# Reflectance_Sensors_SCH.net
KiCad netlist of a schematic drawn in Altium Designer
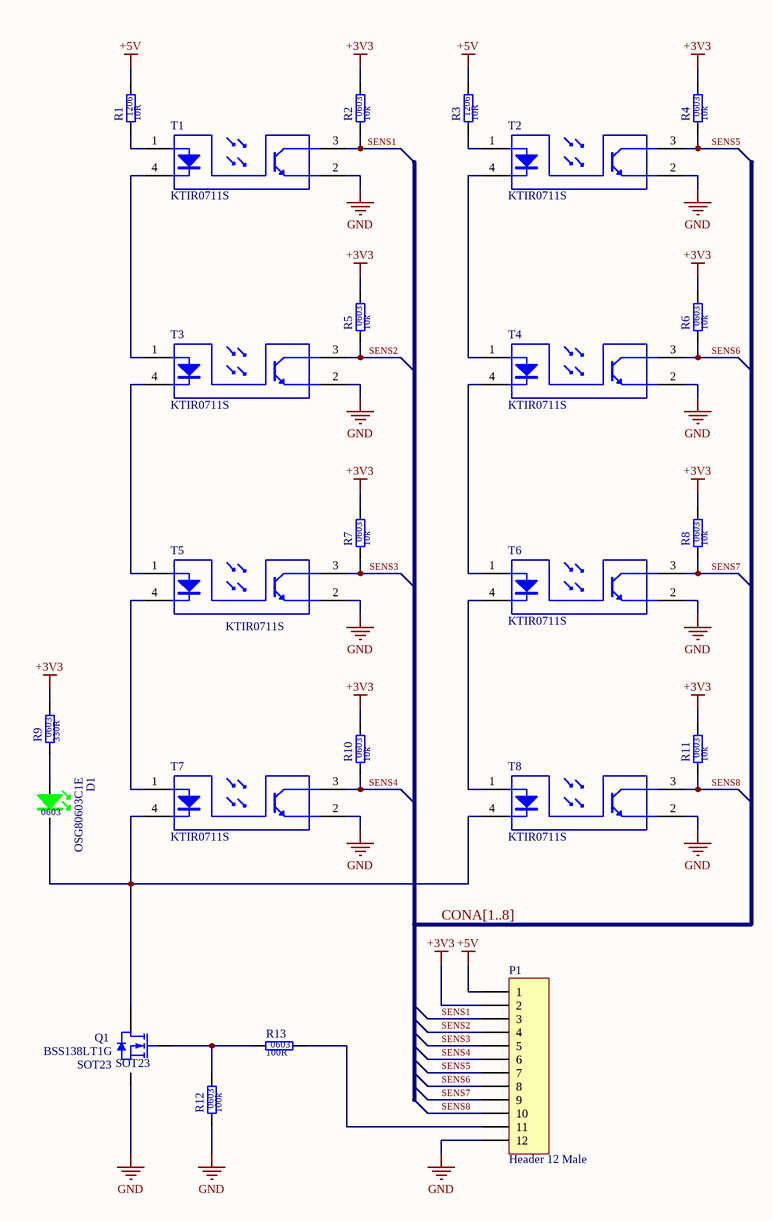
[diagram p0: Reflectance_Sensors_SCH.SchDoc]

(export (version "E")
  (design (tool "Eeschema 10.0.6"))
  (components
    (comp (ref "D1")
      (value "OSG80603C1E")
      (footprint "OL_0603_1608")
      (description "LED GREEN")
      (fields
        (field (name "SCH_FOOTPRINT") "0603")
        (field (name "PART NUMBER") "OL_G_0603_OSG80603C1E")
        (field (name "MANUFACTURER") "Optosupply")
      )
      (libsource (lib "Library") (part "OL_G"))
    )
    (comp (ref "P1")
      (value "Header 12 Male")
      (footprint "H1X12_LONG")
      (description "Header, 12-Pin")
      (libsource (lib "Miscellaneous Connectors") (part "Header 12"))
    )
    (comp (ref "Q1")
      (value "BSS138LT1G")
      (footprint "SOT23_TO236_SC59")
      (fields
        (field (name "PART NUMBER") "QNS_BSS138LT1G_50V_0A2")
        (field (name "SCH_FOOTPRINT") "SOT23")
        (field (name "VOLTAGE") "50V")
        (field (name "MANUFACTURER") "ON Semiconductor")
      )
      (libsource (lib "Library") (part "QN_GSD"))
    )
    (comp (ref "R1")
      (value "10R")
      (footprint "R_1206")
      (fields
        (field (name "SCH_FOOTPRINT") "1206")
        (field (name "PART NUMBER") "R_10R_1206_1")
        (field (name "VOLTAGE") "200V")
        (field (name "POWER") "250mW")
      )
      (libsource (lib "Library") (part "R"))
    )
    (comp (ref "R2")
      (value "10k")
      (footprint "R_0603")
      (fields
        (field (name "SCH_FOOTPRINT") "0603")
        (field (name "PART NUMBER") "R_10k_0603_1")
        (field (name "VOLTAGE") "75V")
        (field (name "POWER") "100mW")
      )
      (libsource (lib "Library") (part "R"))
    )
    (comp (ref "R3")
      (value "10R")
      (footprint "R_1206")
      (fields
        (field (name "SCH_FOOTPRINT") "1206")
        (field (name "PART NUMBER") "R_10R_1206_1")
        (field (name "VOLTAGE") "200V")
        (field (name "POWER") "250mW")
      )
      (libsource (lib "Library") (part "R"))
    )
    (comp (ref "R4")
      (value "10k")
      (footprint "R_0603")
      (fields
        (field (name "SCH_FOOTPRINT") "0603")
        (field (name "PART NUMBER") "R_10k_0603_1")
        (field (name "VOLTAGE") "75V")
        (field (name "POWER") "100mW")
      )
      (libsource (lib "Library") (part "R"))
    )
    (comp (ref "R5")
      (value "10k")
      (footprint "R_0603")
      (fields
        (field (name "SCH_FOOTPRINT") "0603")
        (field (name "PART NUMBER") "R_10k_0603_1")
        (field (name "VOLTAGE") "75V")
        (field (name "POWER") "100mW")
      )
      (libsource (lib "Library") (part "R"))
    )
    (comp (ref "R6")
      (value "10k")
      (footprint "R_0603")
      (fields
        (field (name "SCH_FOOTPRINT") "0603")
        (field (name "PART NUMBER") "R_10k_0603_1")
        (field (name "VOLTAGE") "75V")
        (field (name "POWER") "100mW")
      )
      (libsource (lib "Library") (part "R"))
    )
    (comp (ref "R7")
      (value "10k")
      (footprint "R_0603")
      (fields
        (field (name "SCH_FOOTPRINT") "0603")
        (field (name "PART NUMBER") "R_10k_0603_1")
        (field (name "VOLTAGE") "75V")
        (field (name "POWER") "100mW")
      )
      (libsource (lib "Library") (part "R"))
    )
    (comp (ref "R8")
      (value "10k")
      (footprint "R_0603")
      (fields
        (field (name "SCH_FOOTPRINT") "0603")
        (field (name "PART NUMBER") "R_10k_0603_1")
        (field (name "VOLTAGE") "75V")
        (field (name "POWER") "100mW")
      )
      (libsource (lib "Library") (part "R"))
    )
    (comp (ref "R9")
      (value "330R")
      (footprint "R_0603")
      (fields
        (field (name "SCH_FOOTPRINT") "0603")
        (field (name "PART NUMBER") "R_330R_0603_1")
        (field (name "VOLTAGE") "50V")
        (field (name "POWER") "100mW")
      )
      (libsource (lib "Library") (part "R"))
    )
    (comp (ref "R10")
      (value "10k")
      (footprint "R_0603")
      (fields
        (field (name "SCH_FOOTPRINT") "0603")
        (field (name "PART NUMBER") "R_10k_0603_1")
        (field (name "VOLTAGE") "75V")
        (field (name "POWER") "100mW")
      )
      (libsource (lib "Library") (part "R"))
    )
    (comp (ref "R11")
      (value "10k")
      (footprint "R_0603")
      (fields
        (field (name "SCH_FOOTPRINT") "0603")
        (field (name "PART NUMBER") "R_10k_0603_1")
        (field (name "VOLTAGE") "75V")
        (field (name "POWER") "100mW")
      )
      (libsource (lib "Library") (part "R"))
    )
    (comp (ref "R12")
      (value "100k")
      (footprint "R_0603")
      (fields
        (field (name "SCH_FOOTPRINT") "0603")
        (field (name "PART NUMBER") "R_100k_0603_1")
        (field (name "VOLTAGE") "50V")
        (field (name "POWER") "100mW")
      )
      (libsource (lib "Library") (part "R"))
    )
    (comp (ref "R13")
      (value "100R")
      (footprint "R_0603")
      (fields
        (field (name "SCH_FOOTPRINT") "0603")
        (field (name "PART NUMBER") "R_100R_0603_1")
        (field (name "VOLTAGE") "50V")
        (field (name "POWER") "100mW")
      )
      (libsource (lib "Library") (part "R"))
    )
    (comp (ref "T1")
      (value "KTIR0711S")
      (footprint "KTIR0711S")
      (libsource (lib "Linefollower") (part "KTIR0711S"))
    )
    (comp (ref "T2")
      (value "KTIR0711S")
      (footprint "KTIR0711S")
      (libsource (lib "Linefollower") (part "KTIR0711S"))
    )
    (comp (ref "T3")
      (value "KTIR0711S")
      (footprint "KTIR0711S")
      (libsource (lib "Linefollower") (part "KTIR0711S"))
    )
    (comp (ref "T4")
      (value "KTIR0711S")
      (footprint "KTIR0711S")
      (libsource (lib "Linefollower") (part "KTIR0711S"))
    )
    (comp (ref "T5")
      (value "KTIR0711S")
      (footprint "KTIR0711S")
      (libsource (lib "Linefollower") (part "KTIR0711S"))
    )
    (comp (ref "T6")
      (value "KTIR0711S")
      (footprint "KTIR0711S")
      (libsource (lib "Linefollower") (part "KTIR0711S"))
    )
    (comp (ref "T7")
      (value "KTIR0711S")
      (footprint "KTIR0711S")
      (libsource (lib "Linefollower") (part "KTIR0711S"))
    )
    (comp (ref "T8")
      (value "KTIR0711S")
      (footprint "KTIR0711S")
      (libsource (lib "Linefollower") (part "KTIR0711S"))
    )
  )
  (nets
    (net (code "9") (name "+3V3") (class "Default")
      (node (ref "P1") (pin "2") (pinfunction "2_2") (pintype "passive"))
      (node (ref "R10") (pin "2") (pinfunction "2_2") (pintype "passive"))
      (node (ref "R11") (pin "2") (pinfunction "2_2") (pintype "passive"))
      (node (ref "R2") (pin "2") (pinfunction "2_2") (pintype "passive"))
      (node (ref "R4") (pin "2") (pinfunction "2_2") (pintype "passive"))
      (node (ref "R5") (pin "2") (pinfunction "2_2") (pintype "passive"))
      (node (ref "R6") (pin "2") (pinfunction "2_2") (pintype "passive"))
      (node (ref "R7") (pin "2") (pinfunction "2_2") (pintype "passive"))
      (node (ref "R8") (pin "2") (pinfunction "2_2") (pintype "passive"))
      (node (ref "R9") (pin "2") (pinfunction "2_2") (pintype "passive"))
    )
    (net (code "10") (name "+5V") (class "Default")
      (node (ref "P1") (pin "1") (pinfunction "1_1") (pintype "passive"))
      (node (ref "R1") (pin "2") (pinfunction "2_2") (pintype "passive"))
      (node (ref "R3") (pin "2") (pinfunction "2_2") (pintype "passive"))
    )
    (net (code "12") (name "/SENS1") (class "Default")
      (node (ref "P1") (pin "3") (pinfunction "3_3") (pintype "passive"))
      (node (ref "R2") (pin "1") (pinfunction "1_1") (pintype "passive"))
      (node (ref "T1") (pin "3") (pinfunction "C_3") (pintype "passive"))
    )
    (net (code "13") (name "/SENS2") (class "Default")
      (node (ref "P1") (pin "4") (pinfunction "4_4") (pintype "passive"))
      (node (ref "R5") (pin "1") (pinfunction "1_1") (pintype "passive"))
      (node (ref "T3") (pin "3") (pinfunction "C_3") (pintype "passive"))
    )
    (net (code "14") (name "/SENS3") (class "Default")
      (node (ref "P1") (pin "5") (pinfunction "5_5") (pintype "passive"))
      (node (ref "R7") (pin "1") (pinfunction "1_1") (pintype "passive"))
      (node (ref "T5") (pin "3") (pinfunction "C_3") (pintype "passive"))
    )
    (net (code "15") (name "/SENS4") (class "Default")
      (node (ref "P1") (pin "6") (pinfunction "6_6") (pintype "passive"))
      (node (ref "R10") (pin "1") (pinfunction "1_1") (pintype "passive"))
      (node (ref "T7") (pin "3") (pinfunction "C_3") (pintype "passive"))
    )
    (net (code "16") (name "/SENS5") (class "Default")
      (node (ref "P1") (pin "7") (pinfunction "7_7") (pintype "passive"))
      (node (ref "R4") (pin "1") (pinfunction "1_1") (pintype "passive"))
      (node (ref "T2") (pin "3") (pinfunction "C_3") (pintype "passive"))
    )
    (net (code "17") (name "/SENS6") (class "Default")
      (node (ref "P1") (pin "8") (pinfunction "8_8") (pintype "passive"))
      (node (ref "R6") (pin "1") (pinfunction "1_1") (pintype "passive"))
      (node (ref "T4") (pin "3") (pinfunction "C_3") (pintype "passive"))
    )
    (net (code "18") (name "/SENS7") (class "Default")
      (node (ref "P1") (pin "9") (pinfunction "9_9") (pintype "passive"))
      (node (ref "R8") (pin "1") (pinfunction "1_1") (pintype "passive"))
      (node (ref "T6") (pin "3") (pinfunction "C_3") (pintype "passive"))
    )
    (net (code "19") (name "/SENS8") (class "Default")
      (node (ref "P1") (pin "10") (pinfunction "10_10") (pintype "passive"))
      (node (ref "R11") (pin "1") (pinfunction "1_1") (pintype "passive"))
      (node (ref "T8") (pin "3") (pinfunction "C_3") (pintype "passive"))
    )
    (net (code "20") (name "GND") (class "Default")
      (node (ref "P1") (pin "12") (pinfunction "12_12") (pintype "passive"))
      (node (ref "Q1") (pin "2") (pinfunction "S_2") (pintype "passive"))
      (node (ref "R12") (pin "1") (pinfunction "1_1") (pintype "passive"))
      (node (ref "T1") (pin "2") (pinfunction "E_2") (pintype "passive"))
      (node (ref "T2") (pin "2") (pinfunction "E_2") (pintype "passive"))
      (node (ref "T3") (pin "2") (pinfunction "E_2") (pintype "passive"))
      (node (ref "T4") (pin "2") (pinfunction "E_2") (pintype "passive"))
      (node (ref "T5") (pin "2") (pinfunction "E_2") (pintype "passive"))
      (node (ref "T6") (pin "2") (pinfunction "E_2") (pintype "passive"))
      (node (ref "T7") (pin "2") (pinfunction "E_2") (pintype "passive"))
      (node (ref "T8") (pin "2") (pinfunction "E_2") (pintype "passive"))
    )
    (net (code "21") (name "Net-(D1-A)") (class "Default")
      (node (ref "D1") (pin "2") (pinfunction "A_2") (pintype "passive"))
      (node (ref "R9") (pin "1") (pinfunction "1_1") (pintype "passive"))
    )
    (net (code "22") (name "Net-(D1-K)") (class "Default")
      (node (ref "D1") (pin "1") (pinfunction "K_1") (pintype "passive"))
      (node (ref "Q1") (pin "3") (pinfunction "D_3") (pintype "passive"))
      (node (ref "T7") (pin "4") (pinfunction "K_4") (pintype "passive"))
      (node (ref "T8") (pin "4") (pinfunction "K_4") (pintype "passive"))
    )
    (net (code "23") (name "Net-(P1-Pad11)") (class "Default")
      (node (ref "P1") (pin "11") (pinfunction "11_11") (pintype "passive"))
      (node (ref "R13") (pin "2") (pinfunction "2_2") (pintype "passive"))
    )
    (net (code "24") (name "Net-(Q1-G)") (class "Default")
      (node (ref "Q1") (pin "1") (pinfunction "G_1") (pintype "passive"))
      (node (ref "R12") (pin "2") (pinfunction "2_2") (pintype "passive"))
      (node (ref "R13") (pin "1") (pinfunction "1_1") (pintype "passive"))
    )
    (net (code "25") (name "Net-(T1-A)") (class "Default")
      (node (ref "R1") (pin "1") (pinfunction "1_1") (pintype "passive"))
      (node (ref "T1") (pin "1") (pinfunction "A_1") (pintype "passive"))
    )
    (net (code "26") (name "Net-(T1-K)") (class "Default")
      (node (ref "T1") (pin "4") (pinfunction "K_4") (pintype "passive"))
      (node (ref "T3") (pin "1") (pinfunction "A_1") (pintype "passive"))
    )
    (net (code "27") (name "Net-(T2-A)") (class "Default")
      (node (ref "R3") (pin "1") (pinfunction "1_1") (pintype "passive"))
      (node (ref "T2") (pin "1") (pinfunction "A_1") (pintype "passive"))
    )
    (net (code "28") (name "Net-(T2-K)") (class "Default")
      (node (ref "T2") (pin "4") (pinfunction "K_4") (pintype "passive"))
      (node (ref "T4") (pin "1") (pinfunction "A_1") (pintype "passive"))
    )
    (net (code "29") (name "Net-(T3-K)") (class "Default")
      (node (ref "T3") (pin "4") (pinfunction "K_4") (pintype "passive"))
      (node (ref "T5") (pin "1") (pinfunction "A_1") (pintype "passive"))
    )
    (net (code "30") (name "Net-(T4-K)") (class "Default")
      (node (ref "T4") (pin "4") (pinfunction "K_4") (pintype "passive"))
      (node (ref "T6") (pin "1") (pinfunction "A_1") (pintype "passive"))
    )
    (net (code "31") (name "Net-(T5-K)") (class "Default")
      (node (ref "T5") (pin "4") (pinfunction "K_4") (pintype "passive"))
      (node (ref "T7") (pin "1") (pinfunction "A_1") (pintype "passive"))
    )
    (net (code "32") (name "Net-(T6-K)") (class "Default")
      (node (ref "T6") (pin "4") (pinfunction "K_4") (pintype "passive"))
      (node (ref "T8") (pin "1") (pinfunction "A_1") (pintype "passive"))
    )
  )
)
